# Board_Jadwal_v2.net
KiCad netlist of a schematic drawn in EAGLE
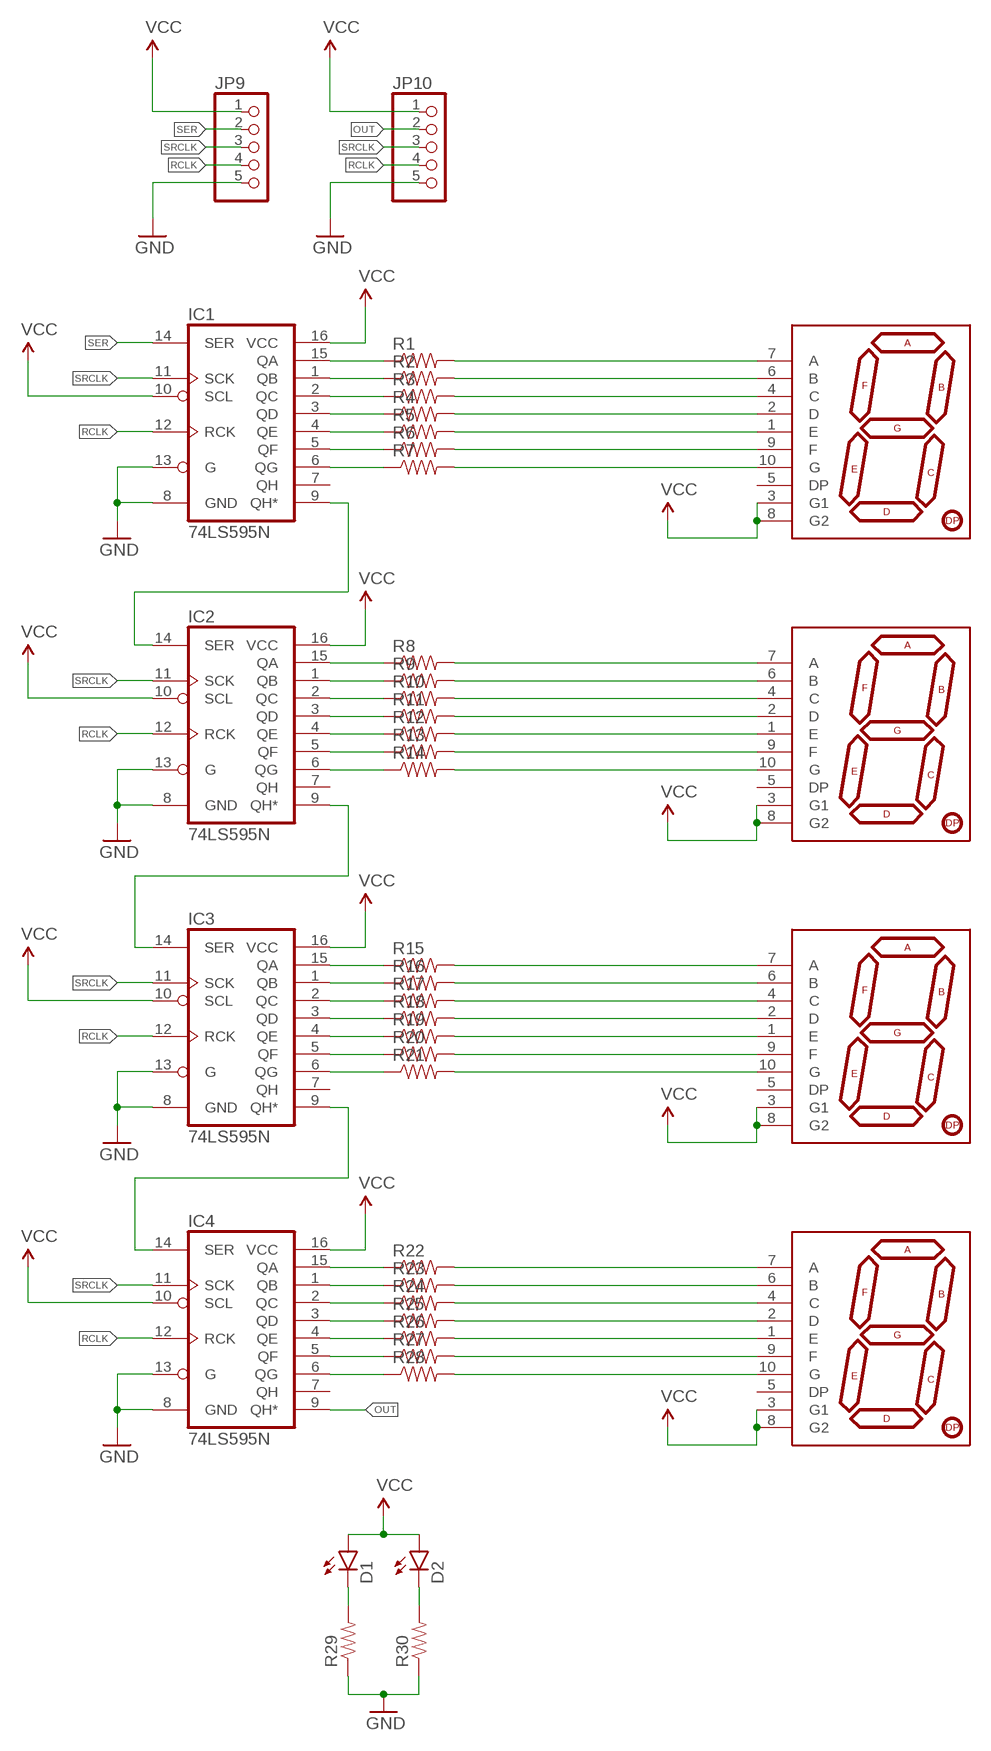
[diagram p0: schematic, sheet 1]

(export (version "E")
  (design (tool "Eeschema 10.0.6"))
  (components
    (comp (ref "D1")
      (value "LED3MM")
      (footprint "eagle-import:LED3MM")
      (libsource (lib "eagle-import") (part "LED3MM"))
    )
    (comp (ref "D2")
      (value "LED3MM")
      (footprint "eagle-import:LED3MM")
      (libsource (lib "eagle-import") (part "LED3MM"))
    )
    (comp (ref "IC1")
      (value "74LS595N")
      (footprint "eagle-import:DIL16")
      (libsource (lib "eagle-import") (part "74595NLS"))
    )
    (comp (ref "IC2")
      (value "74LS595N")
      (footprint "eagle-import:DIL16")
      (libsource (lib "eagle-import") (part "74595NLS"))
    )
    (comp (ref "IC3")
      (value "74LS595N")
      (footprint "eagle-import:DIL16")
      (libsource (lib "eagle-import") (part "74595NLS"))
    )
    (comp (ref "IC4")
      (value "74LS595N")
      (footprint "eagle-import:DIL16")
      (libsource (lib "eagle-import") (part "74595NLS"))
    )
    (comp (ref "JP9")
      (value "PINHD-1X5")
      (footprint "eagle-import:1X05")
      (libsource (lib "eagle-import") (part "PINHD-1X5"))
    )
    (comp (ref "JP10")
      (value "PINHD-1X5")
      (footprint "eagle-import:1X05")
      (libsource (lib "eagle-import") (part "PINHD-1X5"))
    )
    (comp (ref "R1")
      (value "RESISTORPTH-1/4W")
      (footprint "eagle-import:AXIAL-0.4")
      (libsource (lib "eagle-import") (part "RESISTORPTH-1/4W"))
    )
    (comp (ref "R2")
      (value "RESISTORPTH-1/4W")
      (footprint "eagle-import:AXIAL-0.4")
      (libsource (lib "eagle-import") (part "RESISTORPTH-1/4W"))
    )
    (comp (ref "R3")
      (value "RESISTORPTH-1/4W")
      (footprint "eagle-import:AXIAL-0.4")
      (libsource (lib "eagle-import") (part "RESISTORPTH-1/4W"))
    )
    (comp (ref "R4")
      (value "RESISTORPTH-1/4W")
      (footprint "eagle-import:AXIAL-0.4")
      (libsource (lib "eagle-import") (part "RESISTORPTH-1/4W"))
    )
    (comp (ref "R5")
      (value "RESISTORPTH-1/4W")
      (footprint "eagle-import:AXIAL-0.4")
      (libsource (lib "eagle-import") (part "RESISTORPTH-1/4W"))
    )
    (comp (ref "R6")
      (value "RESISTORPTH-1/4W")
      (footprint "eagle-import:AXIAL-0.4")
      (libsource (lib "eagle-import") (part "RESISTORPTH-1/4W"))
    )
    (comp (ref "R7")
      (value "RESISTORPTH-1/4W")
      (footprint "eagle-import:AXIAL-0.4")
      (libsource (lib "eagle-import") (part "RESISTORPTH-1/4W"))
    )
    (comp (ref "R8")
      (value "RESISTORPTH-1/4W")
      (footprint "eagle-import:AXIAL-0.4")
      (libsource (lib "eagle-import") (part "RESISTORPTH-1/4W"))
    )
    (comp (ref "R9")
      (value "RESISTORPTH-1/4W")
      (footprint "eagle-import:AXIAL-0.4")
      (libsource (lib "eagle-import") (part "RESISTORPTH-1/4W"))
    )
    (comp (ref "R10")
      (value "RESISTORPTH-1/4W")
      (footprint "eagle-import:AXIAL-0.4")
      (libsource (lib "eagle-import") (part "RESISTORPTH-1/4W"))
    )
    (comp (ref "R11")
      (value "RESISTORPTH-1/4W")
      (footprint "eagle-import:AXIAL-0.4")
      (libsource (lib "eagle-import") (part "RESISTORPTH-1/4W"))
    )
    (comp (ref "R12")
      (value "RESISTORPTH-1/4W")
      (footprint "eagle-import:AXIAL-0.4")
      (libsource (lib "eagle-import") (part "RESISTORPTH-1/4W"))
    )
    (comp (ref "R13")
      (value "RESISTORPTH-1/4W")
      (footprint "eagle-import:AXIAL-0.4")
      (libsource (lib "eagle-import") (part "RESISTORPTH-1/4W"))
    )
    (comp (ref "R14")
      (value "RESISTORPTH-1/4W")
      (footprint "eagle-import:AXIAL-0.4")
      (libsource (lib "eagle-import") (part "RESISTORPTH-1/4W"))
    )
    (comp (ref "R15")
      (value "RESISTORPTH-1/4W")
      (footprint "eagle-import:AXIAL-0.4")
      (libsource (lib "eagle-import") (part "RESISTORPTH-1/4W"))
    )
    (comp (ref "R16")
      (value "RESISTORPTH-1/4W")
      (footprint "eagle-import:AXIAL-0.4")
      (libsource (lib "eagle-import") (part "RESISTORPTH-1/4W"))
    )
    (comp (ref "R17")
      (value "RESISTORPTH-1/4W")
      (footprint "eagle-import:AXIAL-0.4")
      (libsource (lib "eagle-import") (part "RESISTORPTH-1/4W"))
    )
    (comp (ref "R18")
      (value "RESISTORPTH-1/4W")
      (footprint "eagle-import:AXIAL-0.4")
      (libsource (lib "eagle-import") (part "RESISTORPTH-1/4W"))
    )
    (comp (ref "R19")
      (value "RESISTORPTH-1/4W")
      (footprint "eagle-import:AXIAL-0.4")
      (libsource (lib "eagle-import") (part "RESISTORPTH-1/4W"))
    )
    (comp (ref "R20")
      (value "RESISTORPTH-1/4W")
      (footprint "eagle-import:AXIAL-0.4")
      (libsource (lib "eagle-import") (part "RESISTORPTH-1/4W"))
    )
    (comp (ref "R21")
      (value "RESISTORPTH-1/4W")
      (footprint "eagle-import:AXIAL-0.4")
      (libsource (lib "eagle-import") (part "RESISTORPTH-1/4W"))
    )
    (comp (ref "R22")
      (value "RESISTORPTH-1/4W")
      (footprint "eagle-import:AXIAL-0.4")
      (libsource (lib "eagle-import") (part "RESISTORPTH-1/4W"))
    )
    (comp (ref "R23")
      (value "RESISTORPTH-1/4W")
      (footprint "eagle-import:AXIAL-0.4")
      (libsource (lib "eagle-import") (part "RESISTORPTH-1/4W"))
    )
    (comp (ref "R24")
      (value "RESISTORPTH-1/4W")
      (footprint "eagle-import:AXIAL-0.4")
      (libsource (lib "eagle-import") (part "RESISTORPTH-1/4W"))
    )
    (comp (ref "R25")
      (value "RESISTORPTH-1/4W")
      (footprint "eagle-import:AXIAL-0.4")
      (libsource (lib "eagle-import") (part "RESISTORPTH-1/4W"))
    )
    (comp (ref "R26")
      (value "RESISTORPTH-1/4W")
      (footprint "eagle-import:AXIAL-0.4")
      (libsource (lib "eagle-import") (part "RESISTORPTH-1/4W"))
    )
    (comp (ref "R27")
      (value "RESISTORPTH-1/4W")
      (footprint "eagle-import:AXIAL-0.4")
      (libsource (lib "eagle-import") (part "RESISTORPTH-1/4W"))
    )
    (comp (ref "R28")
      (value "RESISTORPTH-1/4W")
      (footprint "eagle-import:AXIAL-0.4")
      (libsource (lib "eagle-import") (part "RESISTORPTH-1/4W"))
    )
    (comp (ref "R29")
      (value "RESISTORPTH-1/4W")
      (footprint "eagle-import:AXIAL-0.4")
      (libsource (lib "eagle-import") (part "RESISTORPTH-1/4W"))
    )
    (comp (ref "R30")
      (value "RESISTORPTH-1/4W")
      (footprint "eagle-import:AXIAL-0.4")
      (libsource (lib "eagle-import") (part "RESISTORPTH-1/4W"))
    )
    (comp (ref "U$1")
      (value "7-SEGMENT-DISPLAY-1\"-REDEZ")
      (footprint "eagle-import:7-SEGMENT-1_PTH-EZ")
      (libsource (lib "eagle-import") (part "7-SEGMENT-DISPLAY-1{dblquote}-REDEZ"))
    )
    (comp (ref "U$2")
      (value "7-SEGMENT-DISPLAY-1\"-REDEZ")
      (footprint "eagle-import:7-SEGMENT-1_PTH-EZ")
      (libsource (lib "eagle-import") (part "7-SEGMENT-DISPLAY-1{dblquote}-REDEZ"))
    )
    (comp (ref "U$3")
      (value "7-SEGMENT-DISPLAY-1\"-REDEZ")
      (footprint "eagle-import:7-SEGMENT-1_PTH-EZ")
      (libsource (lib "eagle-import") (part "7-SEGMENT-DISPLAY-1{dblquote}-REDEZ"))
    )
    (comp (ref "U$4")
      (value "7-SEGMENT-DISPLAY-1\"-REDEZ")
      (footprint "eagle-import:7-SEGMENT-1_PTH-EZ")
      (libsource (lib "eagle-import") (part "7-SEGMENT-DISPLAY-1{dblquote}-REDEZ"))
    )
  )
  (nets
    (net (code "1") (name "GND") (class "Default")
      (node (ref "IC1") (pin "13") (pinfunction "G_13") (pintype "input"))
      (node (ref "IC1") (pin "8") (pinfunction "GND_8") (pintype "power_in"))
      (node (ref "IC2") (pin "13") (pinfunction "G_13") (pintype "input"))
      (node (ref "IC2") (pin "8") (pinfunction "GND_8") (pintype "power_in"))
      (node (ref "IC3") (pin "13") (pinfunction "G_13") (pintype "input"))
      (node (ref "IC3") (pin "8") (pinfunction "GND_8") (pintype "power_in"))
      (node (ref "IC4") (pin "13") (pinfunction "G_13") (pintype "input"))
      (node (ref "IC4") (pin "8") (pinfunction "GND_8") (pintype "power_in"))
      (node (ref "JP10") (pin "5") (pinfunction "5_5") (pintype "passive"))
      (node (ref "JP9") (pin "5") (pinfunction "5_5") (pintype "passive"))
      (node (ref "R29") (pin "P$1") (pinfunction "1_P$1") (pintype "passive"))
      (node (ref "R30") (pin "P$1") (pinfunction "1_P$1") (pintype "passive"))
    )
    (net (code "2") (name "Net-(D1-C)") (class "Default")
      (node (ref "D1") (pin "K") (pinfunction "C_K") (pintype "passive"))
      (node (ref "R29") (pin "P$2") (pinfunction "2_P$2") (pintype "passive"))
    )
    (net (code "3") (name "Net-(D2-C)") (class "Default")
      (node (ref "D2") (pin "K") (pinfunction "C_K") (pintype "passive"))
      (node (ref "R30") (pin "P$2") (pinfunction "2_P$2") (pintype "passive"))
    )
    (net (code "4") (name "Net-(IC1-QA)") (class "Default")
      (node (ref "IC1") (pin "15") (pinfunction "QA_15") (pintype "tri_state"))
      (node (ref "R1") (pin "P$1") (pinfunction "1_P$1") (pintype "passive"))
    )
    (net (code "5") (name "Net-(IC1-QB)") (class "Default")
      (node (ref "IC1") (pin "1") (pinfunction "QB_1") (pintype "tri_state"))
      (node (ref "R2") (pin "P$1") (pinfunction "1_P$1") (pintype "passive"))
    )
    (net (code "6") (name "Net-(IC1-QC)") (class "Default")
      (node (ref "IC1") (pin "2") (pinfunction "QC_2") (pintype "tri_state"))
      (node (ref "R3") (pin "P$1") (pinfunction "1_P$1") (pintype "passive"))
    )
    (net (code "7") (name "Net-(IC1-QD)") (class "Default")
      (node (ref "IC1") (pin "3") (pinfunction "QD_3") (pintype "tri_state"))
      (node (ref "R4") (pin "P$1") (pinfunction "1_P$1") (pintype "passive"))
    )
    (net (code "8") (name "Net-(IC1-QE)") (class "Default")
      (node (ref "IC1") (pin "4") (pinfunction "QE_4") (pintype "tri_state"))
      (node (ref "R5") (pin "P$1") (pinfunction "1_P$1") (pintype "passive"))
    )
    (net (code "9") (name "Net-(IC1-QF)") (class "Default")
      (node (ref "IC1") (pin "5") (pinfunction "QF_5") (pintype "tri_state"))
      (node (ref "R6") (pin "P$1") (pinfunction "1_P$1") (pintype "passive"))
    )
    (net (code "10") (name "Net-(IC1-QG)") (class "Default")
      (node (ref "IC1") (pin "6") (pinfunction "QG_6") (pintype "tri_state"))
      (node (ref "R7") (pin "P$1") (pinfunction "1_P$1") (pintype "passive"))
    )
    (net (code "11") (name "Net-(IC1-QH*)") (class "Default")
      (node (ref "IC1") (pin "9") (pinfunction "QH*_9") (pintype "tri_state"))
      (node (ref "IC2") (pin "14") (pinfunction "SER_14") (pintype "input"))
    )
    (net (code "12") (name "Net-(IC2-QA)") (class "Default")
      (node (ref "IC2") (pin "15") (pinfunction "QA_15") (pintype "tri_state"))
      (node (ref "R8") (pin "P$1") (pinfunction "1_P$1") (pintype "passive"))
    )
    (net (code "13") (name "Net-(IC2-QB)") (class "Default")
      (node (ref "IC2") (pin "1") (pinfunction "QB_1") (pintype "tri_state"))
      (node (ref "R9") (pin "P$1") (pinfunction "1_P$1") (pintype "passive"))
    )
    (net (code "14") (name "Net-(IC2-QC)") (class "Default")
      (node (ref "IC2") (pin "2") (pinfunction "QC_2") (pintype "tri_state"))
      (node (ref "R10") (pin "P$1") (pinfunction "1_P$1") (pintype "passive"))
    )
    (net (code "15") (name "Net-(IC2-QD)") (class "Default")
      (node (ref "IC2") (pin "3") (pinfunction "QD_3") (pintype "tri_state"))
      (node (ref "R11") (pin "P$1") (pinfunction "1_P$1") (pintype "passive"))
    )
    (net (code "16") (name "Net-(IC2-QE)") (class "Default")
      (node (ref "IC2") (pin "4") (pinfunction "QE_4") (pintype "tri_state"))
      (node (ref "R12") (pin "P$1") (pinfunction "1_P$1") (pintype "passive"))
    )
    (net (code "17") (name "Net-(IC2-QF)") (class "Default")
      (node (ref "IC2") (pin "5") (pinfunction "QF_5") (pintype "tri_state"))
      (node (ref "R13") (pin "P$1") (pinfunction "1_P$1") (pintype "passive"))
    )
    (net (code "18") (name "Net-(IC2-QG)") (class "Default")
      (node (ref "IC2") (pin "6") (pinfunction "QG_6") (pintype "tri_state"))
      (node (ref "R14") (pin "P$1") (pinfunction "1_P$1") (pintype "passive"))
    )
    (net (code "19") (name "Net-(IC2-QH*)") (class "Default")
      (node (ref "IC2") (pin "9") (pinfunction "QH*_9") (pintype "tri_state"))
      (node (ref "IC3") (pin "14") (pinfunction "SER_14") (pintype "input"))
    )
    (net (code "20") (name "Net-(IC3-QA)") (class "Default")
      (node (ref "IC3") (pin "15") (pinfunction "QA_15") (pintype "tri_state"))
      (node (ref "R15") (pin "P$1") (pinfunction "1_P$1") (pintype "passive"))
    )
    (net (code "21") (name "Net-(IC3-QB)") (class "Default")
      (node (ref "IC3") (pin "1") (pinfunction "QB_1") (pintype "tri_state"))
      (node (ref "R16") (pin "P$1") (pinfunction "1_P$1") (pintype "passive"))
    )
    (net (code "22") (name "Net-(IC3-QC)") (class "Default")
      (node (ref "IC3") (pin "2") (pinfunction "QC_2") (pintype "tri_state"))
      (node (ref "R17") (pin "P$1") (pinfunction "1_P$1") (pintype "passive"))
    )
    (net (code "23") (name "Net-(IC3-QD)") (class "Default")
      (node (ref "IC3") (pin "3") (pinfunction "QD_3") (pintype "tri_state"))
      (node (ref "R18") (pin "P$1") (pinfunction "1_P$1") (pintype "passive"))
    )
    (net (code "24") (name "Net-(IC3-QE)") (class "Default")
      (node (ref "IC3") (pin "4") (pinfunction "QE_4") (pintype "tri_state"))
      (node (ref "R19") (pin "P$1") (pinfunction "1_P$1") (pintype "passive"))
    )
    (net (code "25") (name "Net-(IC3-QF)") (class "Default")
      (node (ref "IC3") (pin "5") (pinfunction "QF_5") (pintype "tri_state"))
      (node (ref "R20") (pin "P$1") (pinfunction "1_P$1") (pintype "passive"))
    )
    (net (code "26") (name "Net-(IC3-QG)") (class "Default")
      (node (ref "IC3") (pin "6") (pinfunction "QG_6") (pintype "tri_state"))
      (node (ref "R21") (pin "P$1") (pinfunction "1_P$1") (pintype "passive"))
    )
    (net (code "27") (name "Net-(IC3-QH*)") (class "Default")
      (node (ref "IC3") (pin "9") (pinfunction "QH*_9") (pintype "tri_state"))
      (node (ref "IC4") (pin "14") (pinfunction "SER_14") (pintype "input"))
    )
    (net (code "28") (name "Net-(IC4-QA)") (class "Default")
      (node (ref "IC4") (pin "15") (pinfunction "QA_15") (pintype "tri_state"))
      (node (ref "R22") (pin "P$1") (pinfunction "1_P$1") (pintype "passive"))
    )
    (net (code "29") (name "Net-(IC4-QB)") (class "Default")
      (node (ref "IC4") (pin "1") (pinfunction "QB_1") (pintype "tri_state"))
      (node (ref "R23") (pin "P$1") (pinfunction "1_P$1") (pintype "passive"))
    )
    (net (code "30") (name "Net-(IC4-QC)") (class "Default")
      (node (ref "IC4") (pin "2") (pinfunction "QC_2") (pintype "tri_state"))
      (node (ref "R24") (pin "P$1") (pinfunction "1_P$1") (pintype "passive"))
    )
    (net (code "31") (name "Net-(IC4-QD)") (class "Default")
      (node (ref "IC4") (pin "3") (pinfunction "QD_3") (pintype "tri_state"))
      (node (ref "R25") (pin "P$1") (pinfunction "1_P$1") (pintype "passive"))
    )
    (net (code "32") (name "Net-(IC4-QE)") (class "Default")
      (node (ref "IC4") (pin "4") (pinfunction "QE_4") (pintype "tri_state"))
      (node (ref "R26") (pin "P$1") (pinfunction "1_P$1") (pintype "passive"))
    )
    (net (code "33") (name "Net-(IC4-QF)") (class "Default")
      (node (ref "IC4") (pin "5") (pinfunction "QF_5") (pintype "tri_state"))
      (node (ref "R27") (pin "P$1") (pinfunction "1_P$1") (pintype "passive"))
    )
    (net (code "34") (name "Net-(IC4-QG)") (class "Default")
      (node (ref "IC4") (pin "6") (pinfunction "QG_6") (pintype "tri_state"))
      (node (ref "R28") (pin "P$1") (pinfunction "1_P$1") (pintype "passive"))
    )
    (net (code "35") (name "Net-(R1-2)") (class "Default")
      (node (ref "R1") (pin "P$2") (pinfunction "2_P$2") (pintype "passive"))
      (node (ref "U$1") (pin "7") (pinfunction "A_7") (pintype "bidirectional"))
    )
    (net (code "36") (name "Net-(R2-2)") (class "Default")
      (node (ref "R2") (pin "P$2") (pinfunction "2_P$2") (pintype "passive"))
      (node (ref "U$1") (pin "6") (pinfunction "B_6") (pintype "bidirectional"))
    )
    (net (code "37") (name "Net-(R3-2)") (class "Default")
      (node (ref "R3") (pin "P$2") (pinfunction "2_P$2") (pintype "passive"))
      (node (ref "U$1") (pin "4") (pinfunction "C_4") (pintype "bidirectional"))
    )
    (net (code "38") (name "Net-(R4-2)") (class "Default")
      (node (ref "R4") (pin "P$2") (pinfunction "2_P$2") (pintype "passive"))
      (node (ref "U$1") (pin "2") (pinfunction "D_2") (pintype "bidirectional"))
    )
    (net (code "39") (name "Net-(R5-2)") (class "Default")
      (node (ref "R5") (pin "P$2") (pinfunction "2_P$2") (pintype "passive"))
      (node (ref "U$1") (pin "1") (pinfunction "E_1") (pintype "bidirectional"))
    )
    (net (code "40") (name "Net-(R6-2)") (class "Default")
      (node (ref "R6") (pin "P$2") (pinfunction "2_P$2") (pintype "passive"))
      (node (ref "U$1") (pin "9") (pinfunction "F_9") (pintype "bidirectional"))
    )
    (net (code "41") (name "Net-(R7-2)") (class "Default")
      (node (ref "R7") (pin "P$2") (pinfunction "2_P$2") (pintype "passive"))
      (node (ref "U$1") (pin "10") (pinfunction "G_10") (pintype "bidirectional"))
    )
    (net (code "42") (name "Net-(R8-2)") (class "Default")
      (node (ref "R8") (pin "P$2") (pinfunction "2_P$2") (pintype "passive"))
      (node (ref "U$2") (pin "7") (pinfunction "A_7") (pintype "bidirectional"))
    )
    (net (code "43") (name "Net-(R9-2)") (class "Default")
      (node (ref "R9") (pin "P$2") (pinfunction "2_P$2") (pintype "passive"))
      (node (ref "U$2") (pin "6") (pinfunction "B_6") (pintype "bidirectional"))
    )
    (net (code "44") (name "Net-(R10-2)") (class "Default")
      (node (ref "R10") (pin "P$2") (pinfunction "2_P$2") (pintype "passive"))
      (node (ref "U$2") (pin "4") (pinfunction "C_4") (pintype "bidirectional"))
    )
    (net (code "45") (name "Net-(R11-2)") (class "Default")
      (node (ref "R11") (pin "P$2") (pinfunction "2_P$2") (pintype "passive"))
      (node (ref "U$2") (pin "2") (pinfunction "D_2") (pintype "bidirectional"))
    )
    (net (code "46") (name "Net-(R12-2)") (class "Default")
      (node (ref "R12") (pin "P$2") (pinfunction "2_P$2") (pintype "passive"))
      (node (ref "U$2") (pin "1") (pinfunction "E_1") (pintype "bidirectional"))
    )
    (net (code "47") (name "Net-(R13-2)") (class "Default")
      (node (ref "R13") (pin "P$2") (pinfunction "2_P$2") (pintype "passive"))
      (node (ref "U$2") (pin "9") (pinfunction "F_9") (pintype "bidirectional"))
    )
    (net (code "48") (name "Net-(R14-2)") (class "Default")
      (node (ref "R14") (pin "P$2") (pinfunction "2_P$2") (pintype "passive"))
      (node (ref "U$2") (pin "10") (pinfunction "G_10") (pintype "bidirectional"))
    )
    (net (code "49") (name "Net-(R15-2)") (class "Default")
      (node (ref "R15") (pin "P$2") (pinfunction "2_P$2") (pintype "passive"))
      (node (ref "U$3") (pin "7") (pinfunction "A_7") (pintype "bidirectional"))
    )
    (net (code "50") (name "Net-(R16-2)") (class "Default")
      (node (ref "R16") (pin "P$2") (pinfunction "2_P$2") (pintype "passive"))
      (node (ref "U$3") (pin "6") (pinfunction "B_6") (pintype "bidirectional"))
    )
    (net (code "51") (name "Net-(R17-2)") (class "Default")
      (node (ref "R17") (pin "P$2") (pinfunction "2_P$2") (pintype "passive"))
      (node (ref "U$3") (pin "4") (pinfunction "C_4") (pintype "bidirectional"))
    )
    (net (code "52") (name "Net-(R18-2)") (class "Default")
      (node (ref "R18") (pin "P$2") (pinfunction "2_P$2") (pintype "passive"))
      (node (ref "U$3") (pin "2") (pinfunction "D_2") (pintype "bidirectional"))
    )
    (net (code "53") (name "Net-(R19-2)") (class "Default")
      (node (ref "R19") (pin "P$2") (pinfunction "2_P$2") (pintype "passive"))
      (node (ref "U$3") (pin "1") (pinfunction "E_1") (pintype "bidirectional"))
    )
    (net (code "54") (name "Net-(R20-2)") (class "Default")
      (node (ref "R20") (pin "P$2") (pinfunction "2_P$2") (pintype "passive"))
      (node (ref "U$3") (pin "9") (pinfunction "F_9") (pintype "bidirectional"))
    )
    (net (code "55") (name "Net-(R21-2)") (class "Default")
      (node (ref "R21") (pin "P$2") (pinfunction "2_P$2") (pintype "passive"))
      (node (ref "U$3") (pin "10") (pinfunction "G_10") (pintype "bidirectional"))
    )
    (net (code "56") (name "Net-(R22-2)") (class "Default")
      (node (ref "R22") (pin "P$2") (pinfunction "2_P$2") (pintype "passive"))
      (node (ref "U$4") (pin "7") (pinfunction "A_7") (pintype "bidirectional"))
    )
    (net (code "57") (name "Net-(R23-2)") (class "Default")
      (node (ref "R23") (pin "P$2") (pinfunction "2_P$2") (pintype "passive"))
      (node (ref "U$4") (pin "6") (pinfunction "B_6") (pintype "bidirectional"))
    )
    (net (code "58") (name "Net-(R24-2)") (class "Default")
      (node (ref "R24") (pin "P$2") (pinfunction "2_P$2") (pintype "passive"))
      (node (ref "U$4") (pin "4") (pinfunction "C_4") (pintype "bidirectional"))
    )
    (net (code "59") (name "Net-(R25-2)") (class "Default")
      (node (ref "R25") (pin "P$2") (pinfunction "2_P$2") (pintype "passive"))
      (node (ref "U$4") (pin "2") (pinfunction "D_2") (pintype "bidirectional"))
    )
    (net (code "60") (name "Net-(R26-2)") (class "Default")
      (node (ref "R26") (pin "P$2") (pinfunction "2_P$2") (pintype "passive"))
      (node (ref "U$4") (pin "1") (pinfunction "E_1") (pintype "bidirectional"))
    )
    (net (code "61") (name "Net-(R27-2)") (class "Default")
      (node (ref "R27") (pin "P$2") (pinfunction "2_P$2") (pintype "passive"))
      (node (ref "U$4") (pin "9") (pinfunction "F_9") (pintype "bidirectional"))
    )
    (net (code "62") (name "Net-(R28-2)") (class "Default")
      (node (ref "R28") (pin "P$2") (pinfunction "2_P$2") (pintype "passive"))
      (node (ref "U$4") (pin "10") (pinfunction "G_10") (pintype "bidirectional"))
    )
    (net (code "63") (name "OUT") (class "Default")
      (node (ref "IC4") (pin "9") (pinfunction "QH*_9") (pintype "tri_state"))
      (node (ref "JP10") (pin "2") (pinfunction "2_2") (pintype "passive"))
    )
    (net (code "64") (name "RCLK") (class "Default")
      (node (ref "IC1") (pin "12") (pinfunction "RCK_12") (pintype "input"))
      (node (ref "IC2") (pin "12") (pinfunction "RCK_12") (pintype "input"))
      (node (ref "IC3") (pin "12") (pinfunction "RCK_12") (pintype "input"))
      (node (ref "IC4") (pin "12") (pinfunction "RCK_12") (pintype "input"))
      (node (ref "JP10") (pin "4") (pinfunction "4_4") (pintype "passive"))
      (node (ref "JP9") (pin "4") (pinfunction "4_4") (pintype "passive"))
    )
    (net (code "65") (name "SER") (class "Default")
      (node (ref "IC1") (pin "14") (pinfunction "SER_14") (pintype "input"))
      (node (ref "JP9") (pin "2") (pinfunction "2_2") (pintype "passive"))
    )
    (net (code "66") (name "SRCLK") (class "Default")
      (node (ref "IC1") (pin "11") (pinfunction "SCK_11") (pintype "input"))
      (node (ref "IC2") (pin "11") (pinfunction "SCK_11") (pintype "input"))
      (node (ref "IC3") (pin "11") (pinfunction "SCK_11") (pintype "input"))
      (node (ref "IC4") (pin "11") (pinfunction "SCK_11") (pintype "input"))
      (node (ref "JP10") (pin "3") (pinfunction "3_3") (pintype "passive"))
      (node (ref "JP9") (pin "3") (pinfunction "3_3") (pintype "passive"))
    )
    (net (code "67") (name "VCC") (class "Default")
      (node (ref "D1") (pin "A") (pinfunction "A_A") (pintype "passive"))
      (node (ref "D2") (pin "A") (pinfunction "A_A") (pintype "passive"))
      (node (ref "IC1") (pin "10") (pinfunction "SCL_10") (pintype "input"))
      (node (ref "IC1") (pin "16") (pinfunction "VCC_16") (pintype "power_in"))
      (node (ref "IC2") (pin "10") (pinfunction "SCL_10") (pintype "input"))
      (node (ref "IC2") (pin "16") (pinfunction "VCC_16") (pintype "power_in"))
      (node (ref "IC3") (pin "10") (pinfunction "SCL_10") (pintype "input"))
      (node (ref "IC3") (pin "16") (pinfunction "VCC_16") (pintype "power_in"))
      (node (ref "IC4") (pin "10") (pinfunction "SCL_10") (pintype "input"))
      (node (ref "IC4") (pin "16") (pinfunction "VCC_16") (pintype "power_in"))
      (node (ref "JP10") (pin "1") (pinfunction "1_1") (pintype "passive"))
      (node (ref "JP9") (pin "1") (pinfunction "1_1") (pintype "passive"))
      (node (ref "U$1") (pin "3") (pinfunction "G1_3") (pintype "bidirectional"))
      (node (ref "U$1") (pin "8") (pinfunction "G2_8") (pintype "bidirectional"))
      (node (ref "U$2") (pin "3") (pinfunction "G1_3") (pintype "bidirectional"))
      (node (ref "U$2") (pin "8") (pinfunction "G2_8") (pintype "bidirectional"))
      (node (ref "U$3") (pin "3") (pinfunction "G1_3") (pintype "bidirectional"))
      (node (ref "U$3") (pin "8") (pinfunction "G2_8") (pintype "bidirectional"))
      (node (ref "U$4") (pin "3") (pinfunction "G1_3") (pintype "bidirectional"))
      (node (ref "U$4") (pin "8") (pinfunction "G2_8") (pintype "bidirectional"))
    )
    (net (code "68") (name "unconnected-(IC1-QH-Pad7)") (class "Default")
      (node (ref "IC1") (pin "7") (pinfunction "QH_7") (pintype "tri_state"))
    )
    (net (code "69") (name "unconnected-(IC2-QH-Pad7)") (class "Default")
      (node (ref "IC2") (pin "7") (pinfunction "QH_7") (pintype "tri_state"))
    )
    (net (code "70") (name "unconnected-(IC3-QH-Pad7)") (class "Default")
      (node (ref "IC3") (pin "7") (pinfunction "QH_7") (pintype "tri_state"))
    )
    (net (code "71") (name "unconnected-(IC4-QH-Pad7)") (class "Default")
      (node (ref "IC4") (pin "7") (pinfunction "QH_7") (pintype "tri_state"))
    )
    (net (code "72") (name "unconnected-(U$1-DP-Pad5)") (class "Default")
      (node (ref "U$1") (pin "5") (pinfunction "DP_5") (pintype "bidirectional"))
    )
    (net (code "73") (name "unconnected-(U$2-DP-Pad5)") (class "Default")
      (node (ref "U$2") (pin "5") (pinfunction "DP_5") (pintype "bidirectional"))
    )
    (net (code "74") (name "unconnected-(U$3-DP-Pad5)") (class "Default")
      (node (ref "U$3") (pin "5") (pinfunction "DP_5") (pintype "bidirectional"))
    )
    (net (code "75") (name "unconnected-(U$4-DP-Pad5)") (class "Default")
      (node (ref "U$4") (pin "5") (pinfunction "DP_5") (pintype "bidirectional"))
    )
  )
)
